# RaspiOmix.net
KiCad netlist of a schematic drawn in EAGLE
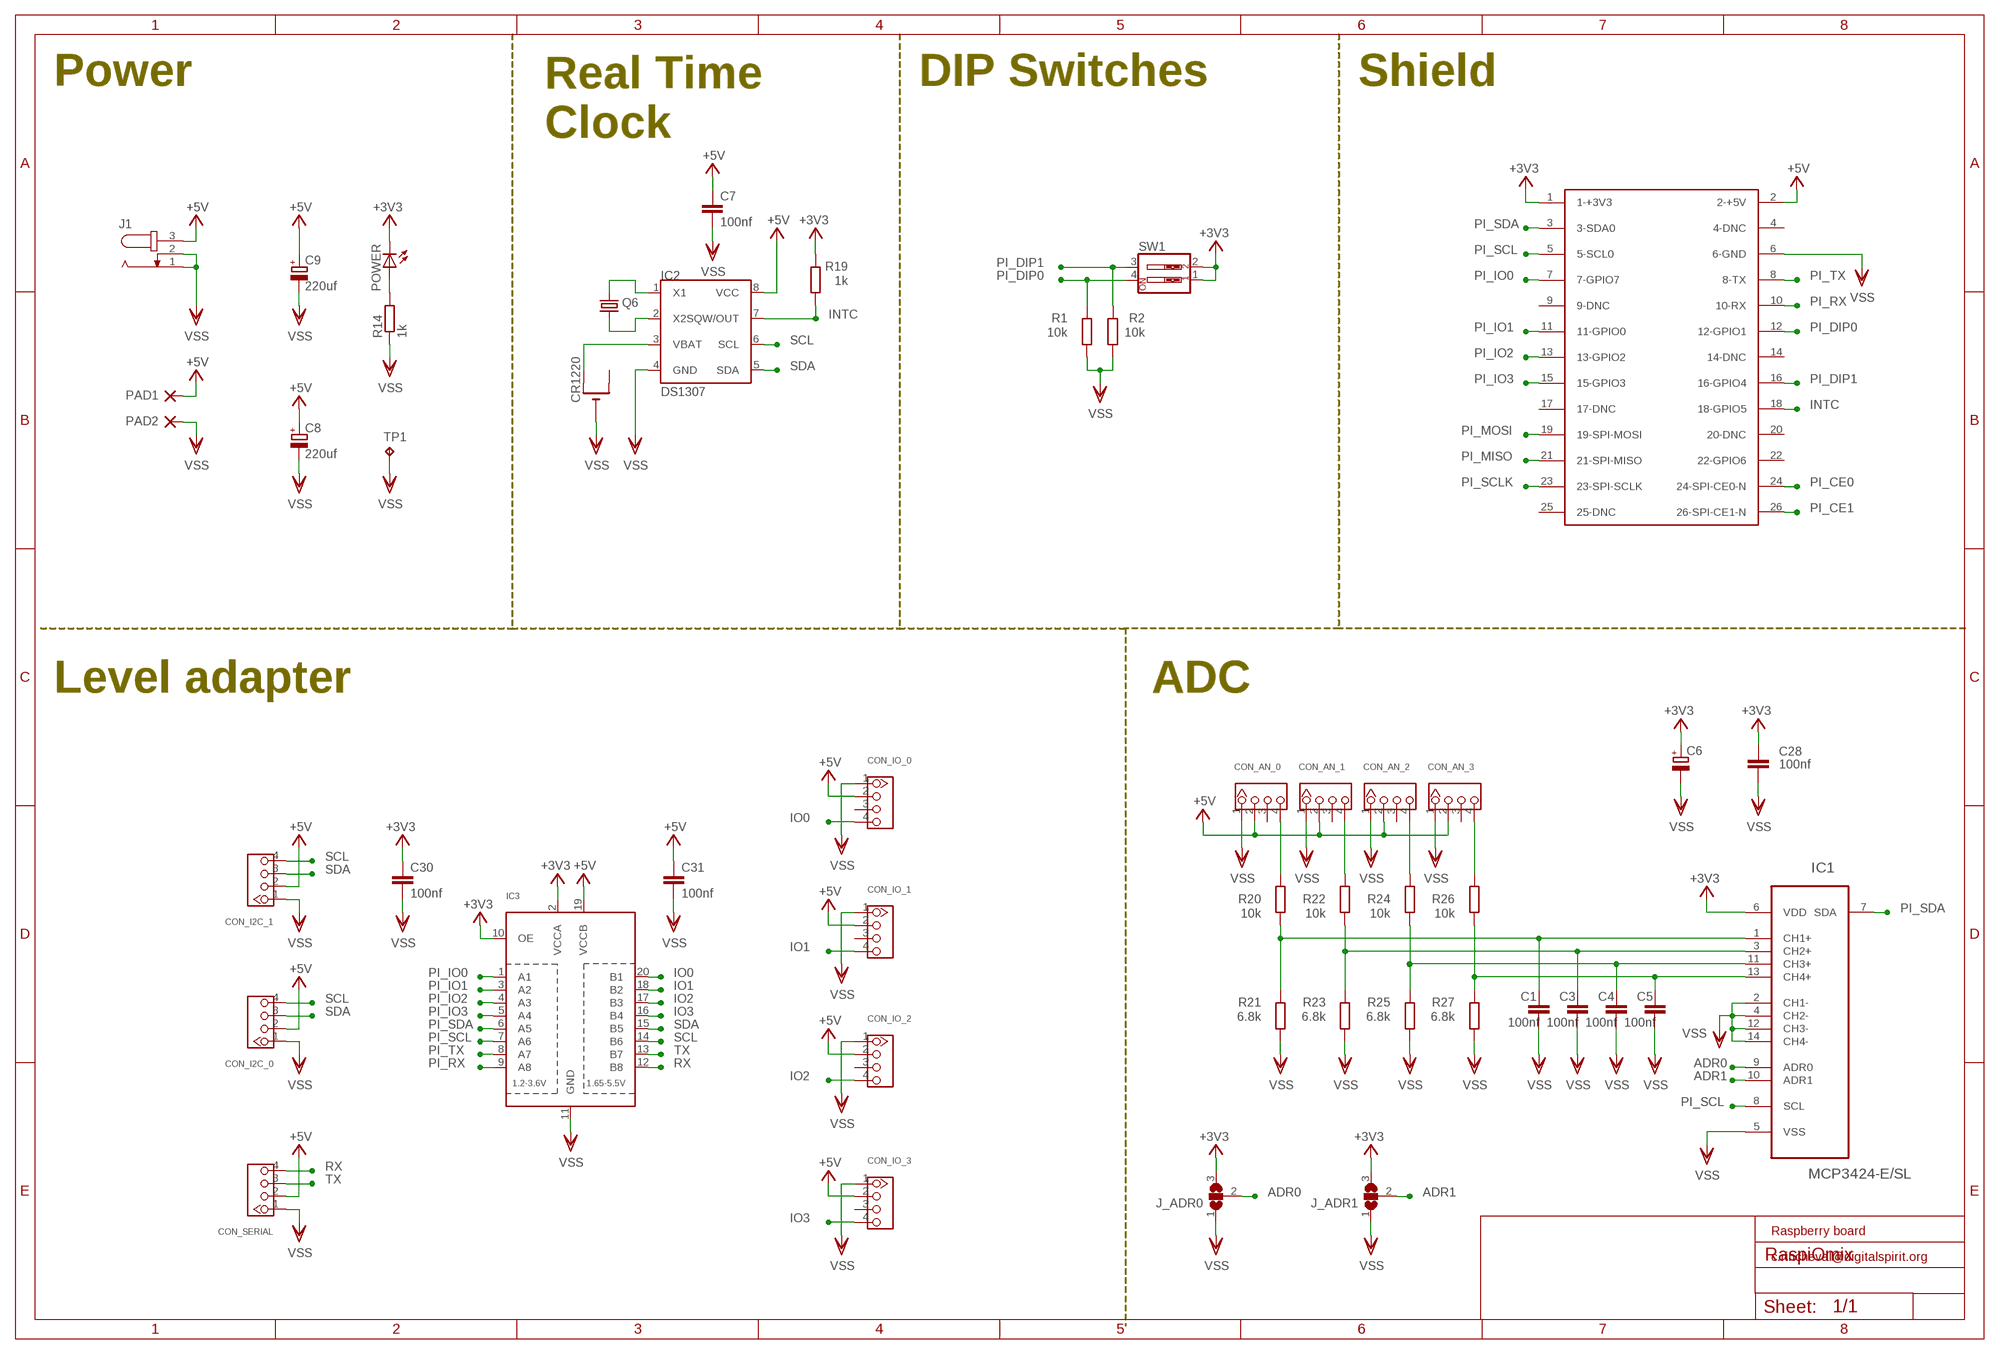
[diagram p0: schematic, sheet 1]

(export (version "E")
  (design (tool "Eeschema 10.0.6"))
  (components
    (comp (ref "C1")
      (value "100nf")
      (footprint "eagle-import:C0805")
      (libsource (lib "eagle-import") (part "C-EUC0805"))
    )
    (comp (ref "C3")
      (value "100nf")
      (footprint "eagle-import:C0805")
      (libsource (lib "eagle-import") (part "C-EUC0805"))
    )
    (comp (ref "C4")
      (value "100nf")
      (footprint "eagle-import:C0805")
      (libsource (lib "eagle-import") (part "C-EUC0805"))
    )
    (comp (ref "C5")
      (value "100nf")
      (footprint "eagle-import:C0805")
      (libsource (lib "eagle-import") (part "C-EUC0805"))
    )
    (comp (ref "C6")
      (value "CPOL-EUB/3528-21R")
      (footprint "eagle-import:B_3528-21R")
      (libsource (lib "eagle-import") (part "CPOL-EUB/3528-21R"))
    )
    (comp (ref "C7")
      (value "100nf")
      (footprint "eagle-import:C0805")
      (libsource (lib "eagle-import") (part "C-EUC0805"))
    )
    (comp (ref "C8")
      (value "220uf")
      (footprint "eagle-import:PANASONIC_D")
      (libsource (lib "eagle-import") (part "CPOL-EUD"))
    )
    (comp (ref "C9")
      (value "220uf")
      (footprint "eagle-import:PANASONIC_D")
      (libsource (lib "eagle-import") (part "CPOL-EUD"))
    )
    (comp (ref "C28")
      (value "100nf")
      (footprint "eagle-import:C0805")
      (libsource (lib "eagle-import") (part "C-EUC0805"))
    )
    (comp (ref "C30")
      (value "100nf")
      (footprint "eagle-import:C0805")
      (libsource (lib "eagle-import") (part "C-EUC0805"))
    )
    (comp (ref "C31")
      (value "100nf")
      (footprint "eagle-import:C0805")
      (libsource (lib "eagle-import") (part "C-EUC0805"))
    )
    (comp (ref "CON_AN_0")
      (value "TWIG-4P-2.0'90D'")
      (footprint "eagle-import:4P-2.0-90D")
      (libsource (lib "eagle-import") (part "TWIG-4P-2.0'90D'"))
    )
    (comp (ref "CON_AN_1")
      (value "TWIG-4P-2.0'90D'")
      (footprint "eagle-import:4P-2.0-90D")
      (libsource (lib "eagle-import") (part "TWIG-4P-2.0'90D'"))
    )
    (comp (ref "CON_AN_2")
      (value "TWIG-4P-2.0'90D'")
      (footprint "eagle-import:4P-2.0-90D")
      (libsource (lib "eagle-import") (part "TWIG-4P-2.0'90D'"))
    )
    (comp (ref "CON_AN_3")
      (value "TWIG-4P-2.0'90D'")
      (footprint "eagle-import:4P-2.0-90D")
      (libsource (lib "eagle-import") (part "TWIG-4P-2.0'90D'"))
    )
    (comp (ref "CON_I2C_0")
      (value "TWIG-4P-2.0'90D'")
      (footprint "eagle-import:4P-2.0-90D")
      (libsource (lib "eagle-import") (part "TWIG-4P-2.0'90D'"))
    )
    (comp (ref "CON_I2C_1")
      (value "TWIG-4P-2.0'90D'")
      (footprint "eagle-import:4P-2.0-90D")
      (libsource (lib "eagle-import") (part "TWIG-4P-2.0'90D'"))
    )
    (comp (ref "CON_IO_0")
      (value "TWIG-4P-2.0'90D'")
      (footprint "eagle-import:4P-2.0-90D")
      (libsource (lib "eagle-import") (part "TWIG-4P-2.0'90D'"))
    )
    (comp (ref "CON_IO_1")
      (value "TWIG-4P-2.0'90D'")
      (footprint "eagle-import:4P-2.0-90D")
      (libsource (lib "eagle-import") (part "TWIG-4P-2.0'90D'"))
    )
    (comp (ref "CON_IO_2")
      (value "TWIG-4P-2.0'90D'")
      (footprint "eagle-import:4P-2.0-90D")
      (libsource (lib "eagle-import") (part "TWIG-4P-2.0'90D'"))
    )
    (comp (ref "CON_IO_3")
      (value "TWIG-4P-2.0'90D'")
      (footprint "eagle-import:4P-2.0-90D")
      (libsource (lib "eagle-import") (part "TWIG-4P-2.0'90D'"))
    )
    (comp (ref "CON_SERIAL")
      (value "TWIG-4P-2.0'90D'")
      (footprint "eagle-import:4P-2.0-90D")
      (libsource (lib "eagle-import") (part "TWIG-4P-2.0'90D'"))
    )
    (comp (ref "CR1220")
      (value "CR1220THM")
      (footprint "eagle-import:CR1220-THM")
      (libsource (lib "eagle-import") (part "CR1220THM"))
    )
    (comp (ref "IC1")
      (value "MCP3424-E/SL")
      (footprint "eagle-import:SOIC-14")
      (libsource (lib "eagle-import") (part "MCP3424-E/SL"))
    )
    (comp (ref "IC2")
      (value "DS1307")
      (footprint "eagle-import:SOIC-8")
      (libsource (lib "eagle-import") (part "DS1307"))
    )
    (comp (ref "IC3")
      (value "TXB0108PWR")
      (footprint "eagle-import:TSSOP20")
      (libsource (lib "eagle-import") (part "TXB0108PWR"))
    )
    (comp (ref "J1")
      (value "JACK-PLUG0")
      (footprint "eagle-import:SPC4077")
      (libsource (lib "eagle-import") (part "JACK-PLUG0"))
    )
    (comp (ref "J_ADR0")
      (value "SJ2W")
      (footprint "eagle-import:SJ_2")
      (libsource (lib "eagle-import") (part "SJ2W"))
    )
    (comp (ref "J_ADR1")
      (value "SJ2W")
      (footprint "eagle-import:SJ_2")
      (libsource (lib "eagle-import") (part "SJ2W"))
    )
    (comp (ref "PAD1")
      (value "WIREPAD3,17/1,3")
      (footprint "eagle-import:3,17_1,3")
      (libsource (lib "eagle-import") (part "WIREPAD3,17/1,3"))
    )
    (comp (ref "PAD2")
      (value "WIREPAD3,17/1,3")
      (footprint "eagle-import:3,17_1,3")
      (libsource (lib "eagle-import") (part "WIREPAD3,17/1,3"))
    )
    (comp (ref "POWER")
      (value "LEDCHIPLED_0805")
      (footprint "eagle-import:CHIPLED_0805")
      (libsource (lib "eagle-import") (part "LEDCHIPLED_0805"))
    )
    (comp (ref "Q6")
      (value "CRYSTALTC26H")
      (footprint "eagle-import:TC26H")
      (libsource (lib "eagle-import") (part "CRYSTALTC26H"))
    )
    (comp (ref "R1")
      (value "10k")
      (footprint "eagle-import:M0805")
      (libsource (lib "eagle-import") (part "R-EU_M0805"))
    )
    (comp (ref "R2")
      (value "10k")
      (footprint "eagle-import:M0805")
      (libsource (lib "eagle-import") (part "R-EU_M0805"))
    )
    (comp (ref "R14")
      (value "1k")
      (footprint "eagle-import:M0805")
      (libsource (lib "eagle-import") (part "R-EU_M0805"))
    )
    (comp (ref "R19")
      (value "1k")
      (footprint "eagle-import:M0805")
      (libsource (lib "eagle-import") (part "R-EU_M0805"))
    )
    (comp (ref "R20")
      (value "10k")
      (footprint "eagle-import:M0805")
      (libsource (lib "eagle-import") (part "R-EU_M0805"))
    )
    (comp (ref "R21")
      (value "6.8k")
      (footprint "eagle-import:M0805")
      (libsource (lib "eagle-import") (part "R-EU_M0805"))
    )
    (comp (ref "R22")
      (value "10k")
      (footprint "eagle-import:M0805")
      (libsource (lib "eagle-import") (part "R-EU_M0805"))
    )
    (comp (ref "R23")
      (value "6.8k")
      (footprint "eagle-import:M0805")
      (libsource (lib "eagle-import") (part "R-EU_M0805"))
    )
    (comp (ref "R24")
      (value "10k")
      (footprint "eagle-import:M0805")
      (libsource (lib "eagle-import") (part "R-EU_M0805"))
    )
    (comp (ref "R25")
      (value "6.8k")
      (footprint "eagle-import:M0805")
      (libsource (lib "eagle-import") (part "R-EU_M0805"))
    )
    (comp (ref "R26")
      (value "10k")
      (footprint "eagle-import:M0805")
      (libsource (lib "eagle-import") (part "R-EU_M0805"))
    )
    (comp (ref "R27")
      (value "6.8k")
      (footprint "eagle-import:M0805")
      (libsource (lib "eagle-import") (part "R-EU_M0805"))
    )
    (comp (ref "SW1")
      (value "SW_DIP-2")
      (footprint "eagle-import:EDG-02")
      (libsource (lib "eagle-import") (part "SW_DIP-2"))
    )
    (comp (ref "TP1")
      (value "TPPAD1-13")
      (footprint "eagle-import:P1-13")
      (libsource (lib "eagle-import") (part "TPPAD1-13"))
    )
    (comp (ref "U$3")
      (value "RASPBERRY-PILIGHT-HOLE")
      (footprint "eagle-import:RASPBERRY-PI-LIGHT-HOLE")
      (libsource (lib "eagle-import") (part "RASPBERRY-PILIGHT-HOLE"))
    )
  )
  (nets
    (net (code "1") (name "+3V3") (class "Default")
      (node (ref "C28") (pin "2") (pinfunction "2_2") (pintype "passive"))
      (node (ref "C30") (pin "1") (pinfunction "1_1") (pintype "passive"))
      (node (ref "C6") (pin "+") (pinfunction "+_+") (pintype "passive"))
      (node (ref "IC1") (pin "6") (pinfunction "VDD_6") (pintype "power_in"))
      (node (ref "IC3") (pin "10") (pinfunction "OE_10") (pintype "bidirectional"))
      (node (ref "IC3") (pin "2") (pinfunction "VCCA_2") (pintype "bidirectional"))
      (node (ref "J_ADR0") (pin "3") (pinfunction "3_3") (pintype "passive"))
      (node (ref "J_ADR1") (pin "3") (pinfunction "3_3") (pintype "passive"))
      (node (ref "POWER") (pin "C") (pinfunction "C_C") (pintype "passive"))
      (node (ref "R19") (pin "2") (pinfunction "2_2") (pintype "passive"))
      (node (ref "SW1") (pin "1") (pinfunction "1_1") (pintype "passive"))
      (node (ref "SW1") (pin "2") (pinfunction "2_2") (pintype "passive"))
      (node (ref "U$3") (pin "1") (pinfunction "1-+3V3_1") (pintype "bidirectional"))
    )
    (net (code "2") (name "+5V") (class "Default")
      (node (ref "C31") (pin "1") (pinfunction "1_1") (pintype "passive"))
      (node (ref "C7") (pin "1") (pinfunction "1_1") (pintype "passive"))
      (node (ref "C8") (pin "+") (pinfunction "+_+") (pintype "passive"))
      (node (ref "C9") (pin "+") (pinfunction "+_+") (pintype "passive"))
      (node (ref "CON_AN_0") (pin "2") (pinfunction "2_2") (pintype "bidirectional"))
      (node (ref "CON_AN_1") (pin "2") (pinfunction "2_2") (pintype "bidirectional"))
      (node (ref "CON_AN_2") (pin "2") (pinfunction "2_2") (pintype "bidirectional"))
      (node (ref "CON_AN_3") (pin "2") (pinfunction "2_2") (pintype "bidirectional"))
      (node (ref "CON_I2C_0") (pin "2") (pinfunction "2_2") (pintype "bidirectional"))
      (node (ref "CON_I2C_1") (pin "2") (pinfunction "2_2") (pintype "bidirectional"))
      (node (ref "CON_IO_0") (pin "2") (pinfunction "2_2") (pintype "bidirectional"))
      (node (ref "CON_IO_1") (pin "2") (pinfunction "2_2") (pintype "bidirectional"))
      (node (ref "CON_IO_2") (pin "2") (pinfunction "2_2") (pintype "bidirectional"))
      (node (ref "CON_IO_3") (pin "2") (pinfunction "2_2") (pintype "bidirectional"))
      (node (ref "CON_SERIAL") (pin "2") (pinfunction "2_2") (pintype "bidirectional"))
      (node (ref "IC2") (pin "8") (pinfunction "VCC_8") (pintype "power_in"))
      (node (ref "IC3") (pin "19") (pinfunction "VCCB_19") (pintype "bidirectional"))
      (node (ref "J1") (pin "3") (pinfunction "3_3") (pintype "passive"))
      (node (ref "PAD1") (pin "1") (pinfunction "P_1") (pintype "passive"))
      (node (ref "U$3") (pin "2") (pinfunction "2-+5V_2") (pintype "bidirectional"))
    )
    (net (code "3") (name "/ADR0") (class "Default")
      (node (ref "IC1") (pin "9") (pinfunction "ADR0_9") (pintype "input"))
      (node (ref "J_ADR0") (pin "2") (pinfunction "2_2") (pintype "passive"))
    )
    (net (code "4") (name "/ADR1") (class "Default")
      (node (ref "IC1") (pin "10") (pinfunction "ADR1_10") (pintype "input"))
      (node (ref "J_ADR1") (pin "2") (pinfunction "2_2") (pintype "passive"))
    )
    (net (code "5") (name "/INTC") (class "Default")
      (node (ref "IC2") (pin "7") (pinfunction "SQW/OUT_7") (pintype "output"))
      (node (ref "R19") (pin "1") (pinfunction "1_1") (pintype "passive"))
      (node (ref "U$3") (pin "18") (pinfunction "18-GPIO5_18") (pintype "bidirectional"))
    )
    (net (code "6") (name "/IO0") (class "Default")
      (node (ref "CON_IO_0") (pin "4") (pinfunction "4_4") (pintype "bidirectional"))
      (node (ref "IC3") (pin "20") (pinfunction "B1_20") (pintype "bidirectional"))
    )
    (net (code "7") (name "/IO1") (class "Default")
      (node (ref "CON_IO_1") (pin "4") (pinfunction "4_4") (pintype "bidirectional"))
      (node (ref "IC3") (pin "18") (pinfunction "B2_18") (pintype "bidirectional"))
    )
    (net (code "8") (name "/IO2") (class "Default")
      (node (ref "CON_IO_2") (pin "4") (pinfunction "4_4") (pintype "bidirectional"))
      (node (ref "IC3") (pin "17") (pinfunction "B3_17") (pintype "bidirectional"))
    )
    (net (code "9") (name "/IO3") (class "Default")
      (node (ref "CON_IO_3") (pin "4") (pinfunction "4_4") (pintype "bidirectional"))
      (node (ref "IC3") (pin "16") (pinfunction "B4_16") (pintype "bidirectional"))
    )
    (net (code "10") (name "/PI_CE0") (class "Default")
      (node (ref "U$3") (pin "24") (pinfunction "24-SPI-CE0-N_24") (pintype "bidirectional"))
    )
    (net (code "11") (name "/PI_CE1") (class "Default")
      (node (ref "U$3") (pin "26") (pinfunction "26-SPI-CE1-N_26") (pintype "bidirectional"))
    )
    (net (code "12") (name "/PI_DIP0") (class "Default")
      (node (ref "R1") (pin "2") (pinfunction "2_2") (pintype "passive"))
      (node (ref "SW1") (pin "4") (pinfunction "4_4") (pintype "passive"))
      (node (ref "U$3") (pin "12") (pinfunction "12-GPIO1_12") (pintype "bidirectional"))
    )
    (net (code "13") (name "/PI_DIP1") (class "Default")
      (node (ref "R2") (pin "2") (pinfunction "2_2") (pintype "passive"))
      (node (ref "SW1") (pin "3") (pinfunction "3_3") (pintype "passive"))
      (node (ref "U$3") (pin "16") (pinfunction "16-GPIO4_16") (pintype "bidirectional"))
    )
    (net (code "14") (name "/PI_IO0") (class "Default")
      (node (ref "IC3") (pin "1") (pinfunction "A1_1") (pintype "bidirectional"))
      (node (ref "U$3") (pin "7") (pinfunction "7-GPIO7_7") (pintype "bidirectional"))
    )
    (net (code "15") (name "/PI_IO1") (class "Default")
      (node (ref "IC3") (pin "3") (pinfunction "A2_3") (pintype "bidirectional"))
      (node (ref "U$3") (pin "11") (pinfunction "11-GPIO0_11") (pintype "bidirectional"))
    )
    (net (code "16") (name "/PI_IO2") (class "Default")
      (node (ref "IC3") (pin "4") (pinfunction "A3_4") (pintype "bidirectional"))
      (node (ref "U$3") (pin "13") (pinfunction "13-GPIO2_13") (pintype "bidirectional"))
    )
    (net (code "17") (name "/PI_IO3") (class "Default")
      (node (ref "IC3") (pin "5") (pinfunction "A4_5") (pintype "bidirectional"))
      (node (ref "U$3") (pin "15") (pinfunction "15-GPIO3_15") (pintype "bidirectional"))
    )
    (net (code "18") (name "/PI_MISO") (class "Default")
      (node (ref "U$3") (pin "21") (pinfunction "21-SPI-MISO_21") (pintype "bidirectional"))
    )
    (net (code "19") (name "/PI_MOSI") (class "Default")
      (node (ref "U$3") (pin "19") (pinfunction "19-SPI-MOSI_19") (pintype "bidirectional"))
    )
    (net (code "20") (name "/PI_RX") (class "Default")
      (node (ref "IC3") (pin "9") (pinfunction "A8_9") (pintype "bidirectional"))
      (node (ref "U$3") (pin "10") (pinfunction "10-RX_10") (pintype "bidirectional"))
    )
    (net (code "21") (name "/PI_SCL") (class "Default")
      (node (ref "IC1") (pin "8") (pinfunction "SCL_8") (pintype "input"))
      (node (ref "IC3") (pin "7") (pinfunction "A6_7") (pintype "bidirectional"))
      (node (ref "U$3") (pin "5") (pinfunction "5-SCL0_5") (pintype "bidirectional"))
    )
    (net (code "22") (name "/PI_SCLK") (class "Default")
      (node (ref "U$3") (pin "23") (pinfunction "23-SPI-SCLK_23") (pintype "bidirectional"))
    )
    (net (code "23") (name "/PI_SDA") (class "Default")
      (node (ref "IC1") (pin "7") (pinfunction "SDA_7") (pintype "bidirectional"))
      (node (ref "IC3") (pin "6") (pinfunction "A5_6") (pintype "bidirectional"))
      (node (ref "U$3") (pin "3") (pinfunction "3-SDA0_3") (pintype "bidirectional"))
    )
    (net (code "24") (name "/PI_TX") (class "Default")
      (node (ref "IC3") (pin "8") (pinfunction "A7_8") (pintype "bidirectional"))
      (node (ref "U$3") (pin "8") (pinfunction "8-TX_8") (pintype "bidirectional"))
    )
    (net (code "25") (name "/RX") (class "Default")
      (node (ref "CON_SERIAL") (pin "4") (pinfunction "4_4") (pintype "bidirectional"))
      (node (ref "IC3") (pin "12") (pinfunction "B8_12") (pintype "bidirectional"))
    )
    (net (code "26") (name "/SCL") (class "Default")
      (node (ref "CON_I2C_0") (pin "4") (pinfunction "4_4") (pintype "bidirectional"))
      (node (ref "CON_I2C_1") (pin "4") (pinfunction "4_4") (pintype "bidirectional"))
      (node (ref "IC2") (pin "6") (pinfunction "SCL_6") (pintype "input"))
      (node (ref "IC3") (pin "14") (pinfunction "B6_14") (pintype "bidirectional"))
    )
    (net (code "27") (name "/SDA") (class "Default")
      (node (ref "CON_I2C_0") (pin "3") (pinfunction "3_3") (pintype "bidirectional"))
      (node (ref "CON_I2C_1") (pin "3") (pinfunction "3_3") (pintype "bidirectional"))
      (node (ref "IC2") (pin "5") (pinfunction "SDA_5") (pintype "bidirectional"))
      (node (ref "IC3") (pin "15") (pinfunction "B5_15") (pintype "bidirectional"))
    )
    (net (code "28") (name "/TX") (class "Default")
      (node (ref "CON_SERIAL") (pin "3") (pinfunction "3_3") (pintype "bidirectional"))
      (node (ref "IC3") (pin "13") (pinfunction "B7_13") (pintype "bidirectional"))
    )
    (net (code "29") (name "Net-(CON_AN_0-Pad4)") (class "Default")
      (node (ref "CON_AN_0") (pin "4") (pinfunction "4_4") (pintype "bidirectional"))
      (node (ref "R20") (pin "2") (pinfunction "2_2") (pintype "passive"))
    )
    (net (code "30") (name "Net-(CON_AN_1-Pad4)") (class "Default")
      (node (ref "CON_AN_1") (pin "4") (pinfunction "4_4") (pintype "bidirectional"))
      (node (ref "R22") (pin "2") (pinfunction "2_2") (pintype "passive"))
    )
    (net (code "31") (name "Net-(CON_AN_2-Pad4)") (class "Default")
      (node (ref "CON_AN_2") (pin "4") (pinfunction "4_4") (pintype "bidirectional"))
      (node (ref "R24") (pin "2") (pinfunction "2_2") (pintype "passive"))
    )
    (net (code "32") (name "Net-(CON_AN_3-Pad4)") (class "Default")
      (node (ref "CON_AN_3") (pin "4") (pinfunction "4_4") (pintype "bidirectional"))
      (node (ref "R26") (pin "2") (pinfunction "2_2") (pintype "passive"))
    )
    (net (code "33") (name "Net-(CR1220-+)") (class "Default")
      (node (ref "CR1220") (pin "+1") (pinfunction "+_+1") (pintype "passive"))
      (node (ref "IC2") (pin "3") (pinfunction "VBAT_3") (pintype "power_in"))
    )
    (net (code "34") (name "Net-(IC1-CH1+)") (class "Default")
      (node (ref "C1") (pin "1") (pinfunction "1_1") (pintype "passive"))
      (node (ref "IC1") (pin "1") (pinfunction "CH1+_1") (pintype "input"))
      (node (ref "R20") (pin "1") (pinfunction "1_1") (pintype "passive"))
      (node (ref "R21") (pin "2") (pinfunction "2_2") (pintype "passive"))
    )
    (net (code "35") (name "Net-(IC1-CH2+)") (class "Default")
      (node (ref "C3") (pin "1") (pinfunction "1_1") (pintype "passive"))
      (node (ref "IC1") (pin "3") (pinfunction "CH2+_3") (pintype "input"))
      (node (ref "R22") (pin "1") (pinfunction "1_1") (pintype "passive"))
      (node (ref "R23") (pin "2") (pinfunction "2_2") (pintype "passive"))
    )
    (net (code "36") (name "Net-(IC1-CH3+)") (class "Default")
      (node (ref "C4") (pin "1") (pinfunction "1_1") (pintype "passive"))
      (node (ref "IC1") (pin "11") (pinfunction "CH3+_11") (pintype "input"))
      (node (ref "R24") (pin "1") (pinfunction "1_1") (pintype "passive"))
      (node (ref "R25") (pin "2") (pinfunction "2_2") (pintype "passive"))
    )
    (net (code "37") (name "Net-(IC1-CH4+)") (class "Default")
      (node (ref "C5") (pin "1") (pinfunction "1_1") (pintype "passive"))
      (node (ref "IC1") (pin "13") (pinfunction "CH4+_13") (pintype "input"))
      (node (ref "R26") (pin "1") (pinfunction "1_1") (pintype "passive"))
      (node (ref "R27") (pin "2") (pinfunction "2_2") (pintype "passive"))
    )
    (net (code "38") (name "Net-(IC2-X1)") (class "Default")
      (node (ref "IC2") (pin "1") (pinfunction "X1_1") (pintype "input"))
      (node (ref "Q6") (pin "1") (pinfunction "1_1") (pintype "passive"))
    )
    (net (code "39") (name "Net-(IC2-X2)") (class "Default")
      (node (ref "IC2") (pin "2") (pinfunction "X2_2") (pintype "output"))
      (node (ref "Q6") (pin "2") (pinfunction "2_2") (pintype "passive"))
    )
    (net (code "40") (name "Net-(POWER-PadA)") (class "Default")
      (node (ref "POWER") (pin "A") (pinfunction "A_A") (pintype "passive"))
      (node (ref "R14") (pin "2") (pinfunction "2_2") (pintype "passive"))
    )
    (net (code "41") (name "VSS") (class "Default")
      (node (ref "C1") (pin "2") (pinfunction "2_2") (pintype "passive"))
      (node (ref "C28") (pin "1") (pinfunction "1_1") (pintype "passive"))
      (node (ref "C3") (pin "2") (pinfunction "2_2") (pintype "passive"))
      (node (ref "C30") (pin "2") (pinfunction "2_2") (pintype "passive"))
      (node (ref "C31") (pin "2") (pinfunction "2_2") (pintype "passive"))
      (node (ref "C4") (pin "2") (pinfunction "2_2") (pintype "passive"))
      (node (ref "C5") (pin "2") (pinfunction "2_2") (pintype "passive"))
      (node (ref "C6") (pin "-") (pinfunction "-_-") (pintype "passive"))
      (node (ref "C7") (pin "2") (pinfunction "2_2") (pintype "passive"))
      (node (ref "C8") (pin "-") (pinfunction "-_-") (pintype "passive"))
      (node (ref "C9") (pin "-") (pinfunction "-_-") (pintype "passive"))
      (node (ref "CON_AN_0") (pin "1") (pinfunction "1_1") (pintype "bidirectional"))
      (node (ref "CON_AN_1") (pin "1") (pinfunction "1_1") (pintype "bidirectional"))
      (node (ref "CON_AN_2") (pin "1") (pinfunction "1_1") (pintype "bidirectional"))
      (node (ref "CON_AN_3") (pin "1") (pinfunction "1_1") (pintype "bidirectional"))
      (node (ref "CON_I2C_0") (pin "1") (pinfunction "1_1") (pintype "bidirectional"))
      (node (ref "CON_I2C_1") (pin "1") (pinfunction "1_1") (pintype "bidirectional"))
      (node (ref "CON_IO_0") (pin "1") (pinfunction "1_1") (pintype "bidirectional"))
      (node (ref "CON_IO_1") (pin "1") (pinfunction "1_1") (pintype "bidirectional"))
      (node (ref "CON_IO_2") (pin "1") (pinfunction "1_1") (pintype "bidirectional"))
      (node (ref "CON_IO_3") (pin "1") (pinfunction "1_1") (pintype "bidirectional"))
      (node (ref "CON_SERIAL") (pin "1") (pinfunction "1_1") (pintype "bidirectional"))
      (node (ref "CR1220") (pin "-") (pinfunction "-_-") (pintype "passive"))
      (node (ref "IC1") (pin "12") (pinfunction "CH3-_12") (pintype "input"))
      (node (ref "IC1") (pin "14") (pinfunction "CH4-_14") (pintype "input"))
      (node (ref "IC1") (pin "2") (pinfunction "CH1-_2") (pintype "input"))
      (node (ref "IC1") (pin "4") (pinfunction "CH2-_4") (pintype "input"))
      (node (ref "IC1") (pin "5") (pinfunction "VSS_5") (pintype "power_in"))
      (node (ref "IC2") (pin "4") (pinfunction "GND_4") (pintype "power_in"))
      (node (ref "IC3") (pin "11") (pinfunction "GND_11") (pintype "bidirectional"))
      (node (ref "J1") (pin "1") (pinfunction "1_1") (pintype "passive"))
      (node (ref "J1") (pin "2") (pinfunction "2_2") (pintype "passive"))
      (node (ref "J_ADR0") (pin "1") (pinfunction "1_1") (pintype "passive"))
      (node (ref "J_ADR1") (pin "1") (pinfunction "1_1") (pintype "passive"))
      (node (ref "PAD2") (pin "1") (pinfunction "P_1") (pintype "passive"))
      (node (ref "R1") (pin "1") (pinfunction "1_1") (pintype "passive"))
      (node (ref "R14") (pin "1") (pinfunction "1_1") (pintype "passive"))
      (node (ref "R2") (pin "1") (pinfunction "1_1") (pintype "passive"))
      (node (ref "R21") (pin "1") (pinfunction "1_1") (pintype "passive"))
      (node (ref "R23") (pin "1") (pinfunction "1_1") (pintype "passive"))
      (node (ref "R25") (pin "1") (pinfunction "1_1") (pintype "passive"))
      (node (ref "R27") (pin "1") (pinfunction "1_1") (pintype "passive"))
      (node (ref "TP1") (pin "TP") (pinfunction "TP_TP") (pintype "input"))
      (node (ref "U$3") (pin "6") (pinfunction "6-GND_6") (pintype "bidirectional"))
    )
    (net (code "42") (name "unconnected-(CON_AN_0-Pad3)") (class "Default")
      (node (ref "CON_AN_0") (pin "3") (pinfunction "3_3") (pintype "bidirectional"))
    )
    (net (code "43") (name "unconnected-(CON_AN_1-Pad3)") (class "Default")
      (node (ref "CON_AN_1") (pin "3") (pinfunction "3_3") (pintype "bidirectional"))
    )
    (net (code "44") (name "unconnected-(CON_AN_2-Pad3)") (class "Default")
      (node (ref "CON_AN_2") (pin "3") (pinfunction "3_3") (pintype "bidirectional"))
    )
    (net (code "45") (name "unconnected-(CON_AN_3-Pad3)") (class "Default")
      (node (ref "CON_AN_3") (pin "3") (pinfunction "3_3") (pintype "bidirectional"))
    )
    (net (code "46") (name "unconnected-(CON_IO_0-Pad3)") (class "Default")
      (node (ref "CON_IO_0") (pin "3") (pinfunction "3_3") (pintype "bidirectional"))
    )
    (net (code "47") (name "unconnected-(CON_IO_1-Pad3)") (class "Default")
      (node (ref "CON_IO_1") (pin "3") (pinfunction "3_3") (pintype "bidirectional"))
    )
    (net (code "48") (name "unconnected-(CON_IO_2-Pad3)") (class "Default")
      (node (ref "CON_IO_2") (pin "3") (pinfunction "3_3") (pintype "bidirectional"))
    )
    (net (code "49") (name "unconnected-(CON_IO_3-Pad3)") (class "Default")
      (node (ref "CON_IO_3") (pin "3") (pinfunction "3_3") (pintype "bidirectional"))
    )
    (net (code "50") (name "unconnected-(CR1220-+1-Pad+2)") (class "Default")
      (node (ref "CR1220") (pin "+2") (pinfunction "+1_+2") (pintype "passive"))
    )
    (net (code "51") (name "unconnected-(U$3-4-DNC-Pad4)") (class "Default")
      (node (ref "U$3") (pin "4") (pinfunction "4-DNC_4") (pintype "bidirectional"))
    )
    (net (code "52") (name "unconnected-(U$3-9-DNC-Pad9)") (class "Default")
      (node (ref "U$3") (pin "9") (pinfunction "9-DNC_9") (pintype "bidirectional"))
    )
    (net (code "53") (name "unconnected-(U$3-14-DNC-Pad14)") (class "Default")
      (node (ref "U$3") (pin "14") (pinfunction "14-DNC_14") (pintype "bidirectional"))
    )
    (net (code "54") (name "unconnected-(U$3-17-DNC-Pad17)") (class "Default")
      (node (ref "U$3") (pin "17") (pinfunction "17-DNC_17") (pintype "bidirectional"))
    )
    (net (code "55") (name "unconnected-(U$3-20-DNC-Pad20)") (class "Default")
      (node (ref "U$3") (pin "20") (pinfunction "20-DNC_20") (pintype "bidirectional"))
    )
    (net (code "56") (name "unconnected-(U$3-22-GPIO6-Pad22)") (class "Default")
      (node (ref "U$3") (pin "22") (pinfunction "22-GPIO6_22") (pintype "bidirectional"))
    )
    (net (code "57") (name "unconnected-(U$3-25-DNC-Pad25)") (class "Default")
      (node (ref "U$3") (pin "25") (pinfunction "25-DNC_25") (pintype "bidirectional"))
    )
  )
)
